# FubarinoMini_v20.net
KiCad netlist of a schematic drawn in EAGLE
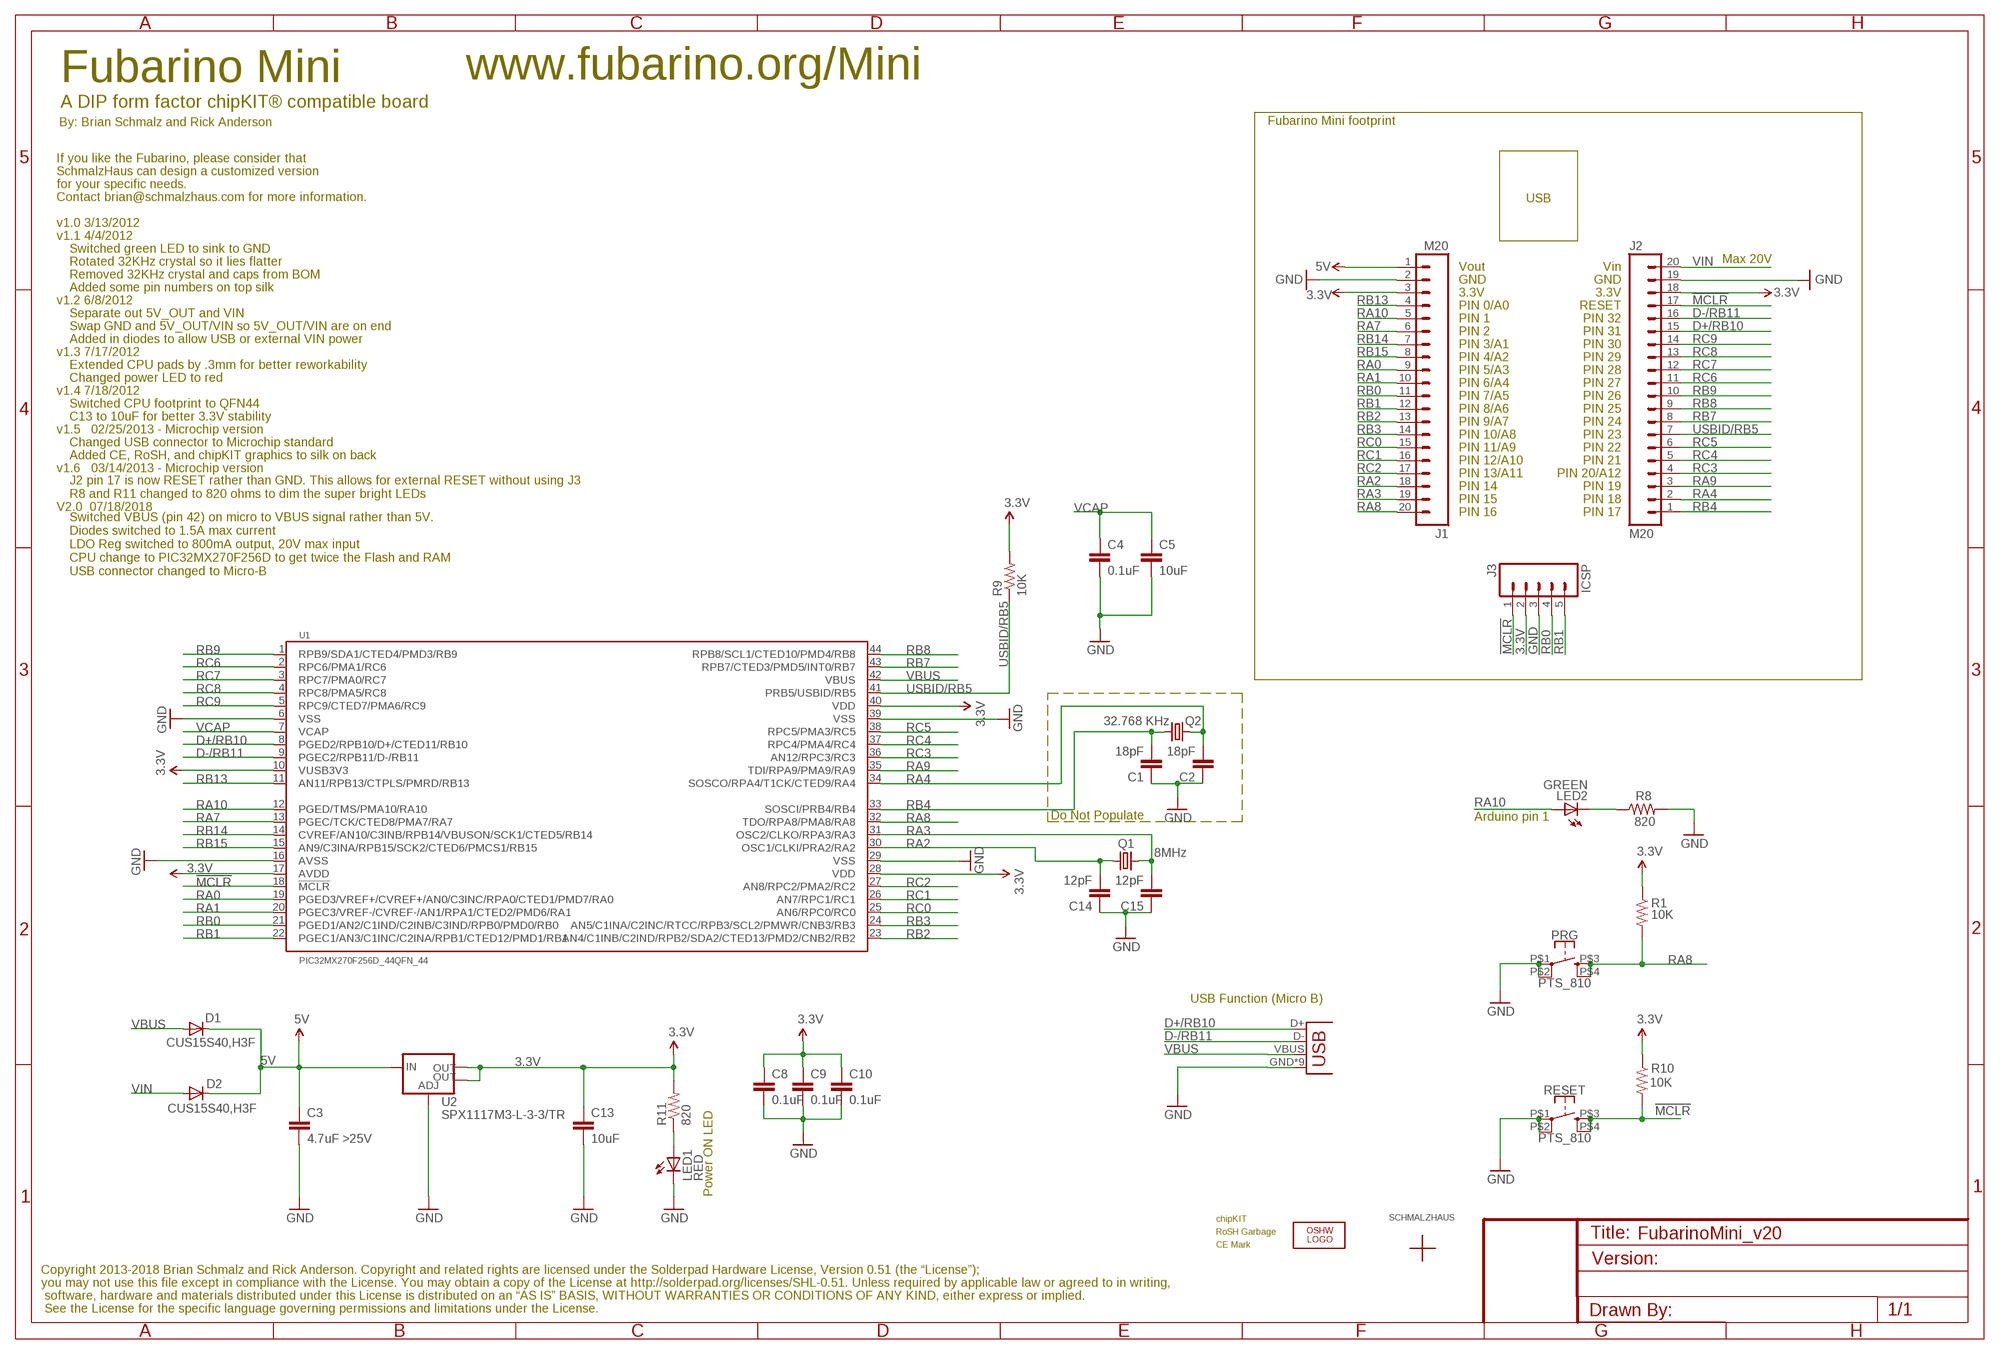
[diagram p0: schematic, sheet 1]

(export (version "E")
  (design (tool "Eeschema 10.0.6"))
  (components
    (comp (ref "C1")
      (value "18pF")
      (footprint "eagle-import:0603-CAP")
      (libsource (lib "eagle-import") (part "SparkFun_CAP0603-CAP"))
    )
    (comp (ref "C2")
      (value "18pF")
      (footprint "eagle-import:0603-CAP")
      (libsource (lib "eagle-import") (part "SparkFun_CAP0603-CAP"))
    )
    (comp (ref "C3")
      (value "4.7uF >25V")
      (footprint "eagle-import:0603-CAP")
      (libsource (lib "eagle-import") (part "SparkFun_CAP0603-CAP"))
    )
    (comp (ref "C4")
      (value "0.1uF")
      (footprint "eagle-import:0603-CAP")
      (libsource (lib "eagle-import") (part "SparkFun_CAP0603-CAP"))
    )
    (comp (ref "C5")
      (value "10uF")
      (footprint "eagle-import:0805")
      (libsource (lib "eagle-import") (part "CAP0805"))
    )
    (comp (ref "C8")
      (value "0.1uF")
      (footprint "eagle-import:0603-CAP")
      (libsource (lib "eagle-import") (part "SparkFun_CAP0603-CAP"))
    )
    (comp (ref "C9")
      (value "0.1uF")
      (footprint "eagle-import:0603-CAP")
      (libsource (lib "eagle-import") (part "SparkFun_CAP0603-CAP"))
    )
    (comp (ref "C10")
      (value "0.1uF")
      (footprint "eagle-import:0603")
      (libsource (lib "eagle-import") (part "CAP0603"))
    )
    (comp (ref "C13")
      (value "10uF")
      (footprint "eagle-import:0805")
      (libsource (lib "eagle-import") (part "SparkFun02-20-08_CAP0805"))
    )
    (comp (ref "C14")
      (value "12pF")
      (footprint "eagle-import:0603-CAP")
      (libsource (lib "eagle-import") (part "SparkFun_CAP0603-CAP"))
    )
    (comp (ref "C15")
      (value "12pF")
      (footprint "eagle-import:0603-CAP")
      (libsource (lib "eagle-import") (part "SparkFun_CAP0603-CAP"))
    )
    (comp (ref "D1")
      (value "CUS15S40,H3F")
      (footprint "eagle-import:SOD-323")
      (libsource (lib "eagle-import") (part "DIODESOD"))
    )
    (comp (ref "D2")
      (value "CUS15S40,H3F")
      (footprint "eagle-import:SOD-323")
      (libsource (lib "eagle-import") (part "DIODESOD"))
    )
    (comp (ref "ICSP")
      (value "J3")
      (footprint "eagle-import:1X05_NOSILK")
      (libsource (lib "eagle-import") (part "M05NOSLILK"))
    )
    (comp (ref "J1")
      (value "M20")
      (footprint "eagle-import:1X20_NO_PIN1")
      (libsource (lib "eagle-import") (part "M20"))
    )
    (comp (ref "J2")
      (value "M20")
      (footprint "eagle-import:1X20_NO_PIN1")
      (libsource (lib "eagle-import") (part "M20"))
    )
    (comp (ref "LED1")
      (value "RED")
      (footprint "eagle-import:LED-0603")
      (libsource (lib "eagle-import") (part "LED0603"))
    )
    (comp (ref "LED2")
      (value "GREEN")
      (footprint "eagle-import:LED-0603")
      (libsource (lib "eagle-import") (part "LED0603"))
    )
    (comp (ref "LOGO1")
      (value "OSHW_LOGO_8MILX0070-NT")
      (footprint "eagle-import:OSHW_8X70_NOTEXT")
      (libsource (lib "eagle-import") (part "OSHW_LOGO_8MILX0070-NT"))
    )
    (comp (ref "PRG")
      (value "PTS_810")
      (footprint "eagle-import:PTS_810")
      (libsource (lib "eagle-import") (part "PTS_810"))
    )
    (comp (ref "Q1")
      (value "8MHz")
      (footprint "eagle-import:NX3225GD")
      (libsource (lib "eagle-import") (part "NX3225GD"))
    )
    (comp (ref "Q2")
      (value "32.768 KHz")
      (footprint "eagle-import:TC26H")
      (libsource (lib "eagle-import") (part "CRYSTALTC26H"))
    )
    (comp (ref "R1")
      (value "10K")
      (footprint "eagle-import:0603-RES")
      (libsource (lib "eagle-import") (part "RESISTOR0603-RES"))
    )
    (comp (ref "R8")
      (value "820")
      (footprint "eagle-import:0603-RES")
      (libsource (lib "eagle-import") (part "RESISTOR0603-RES"))
    )
    (comp (ref "R9")
      (value "10K")
      (footprint "eagle-import:0603-RES")
      (libsource (lib "eagle-import") (part "RESISTOR0603-RES"))
    )
    (comp (ref "R10")
      (value "10K")
      (footprint "eagle-import:0603-RES")
      (libsource (lib "eagle-import") (part "RESISTOR0603-RES"))
    )
    (comp (ref "R11")
      (value "820")
      (footprint "eagle-import:0603-RES")
      (libsource (lib "eagle-import") (part "RESISTOR0603-RES"))
    )
    (comp (ref "RESET")
      (value "PTS_810")
      (footprint "eagle-import:PTS_810")
      (libsource (lib "eagle-import") (part "PTS_810"))
    )
    (comp (ref "U$1")
      (value "SCHMALZHAUSSCHMALZHAUS_SMALL")
      (footprint "eagle-import:SCHMALZHAUS_SMALL")
      (libsource (lib "eagle-import") (part "SCHMALZHAUSSCHMALZHAUS_SMALL"))
    )
    (comp (ref "U$2")
      (value "CE_MARK5MM")
      (footprint "eagle-import:CE_5MM")
      (libsource (lib "eagle-import") (part "CE_MARK5MM"))
    )
    (comp (ref "U$3")
      (value "ROSH_GARBAGE")
      (footprint "eagle-import:ROHS_GARBAGE_5MM")
      (libsource (lib "eagle-import") (part "ROSH_GARBAGE"))
    )
    (comp (ref "U$4")
      (value "CHIPKIT2MM")
      (footprint "eagle-import:CHIPKIT_2MM")
      (libsource (lib "eagle-import") (part "CHIPKIT2MM"))
    )
    (comp (ref "U$5")
      (value "USBMICROB")
      (footprint "eagle-import:USB-MICROB_FCI_PINS")
      (libsource (lib "eagle-import") (part "USBMICROB"))
    )
    (comp (ref "U1")
      (value "PIC32MX270F256D_44QFN_44")
      (footprint "eagle-import:QFN-44-8X8-NOPAD")
      (libsource (lib "eagle-import") (part "PIC32MX2XX_44QFN44"))
    )
    (comp (ref "U2")
      (value "SPX1117M3-L-3-3/TR")
      (footprint "eagle-import:SOT223")
      (libsource (lib "eagle-import") (part "V_REG_LM1117SOT223"))
    )
  )
  (nets
    (net (code "1") (name "/D+{slash}RB10") (class "Default")
      (node (ref "J2") (pin "15") (pinfunction "15_15") (pintype "passive"))
      (node (ref "U$5") (pin "D+") (pinfunction "D+_D+") (pintype "bidirectional"))
      (node (ref "U1") (pin "8") (pinfunction "PGED2/RPB10/D+/CTED11/RB10_8") (pintype "bidirectional"))
    )
    (net (code "2") (name "/D-{slash}RB11") (class "Default")
      (node (ref "J2") (pin "16") (pinfunction "16_16") (pintype "passive"))
      (node (ref "U$5") (pin "D-") (pinfunction "D-_D-") (pintype "bidirectional"))
      (node (ref "U1") (pin "9") (pinfunction "PGEC2/RPB11/D-/RB11_9") (pintype "bidirectional"))
    )
    (net (code "3") (name "/RA0") (class "Default")
      (node (ref "J1") (pin "9") (pinfunction "9_9") (pintype "passive"))
      (node (ref "U1") (pin "19") (pinfunction "PGED3/VREF+/CVREF+/AN0/C3INC/RPA0/CTED1/PMD7/RA0_19") (pintype "bidirectional"))
    )
    (net (code "4") (name "/RA1") (class "Default")
      (node (ref "J1") (pin "10") (pinfunction "10_10") (pintype "passive"))
      (node (ref "U1") (pin "20") (pinfunction "PGEC3/VREF-/CVREF-/AN1/RPA1/CTED2/PMD6/RA1_20") (pintype "bidirectional"))
    )
    (net (code "5") (name "/RA2") (class "Default")
      (node (ref "C14") (pin "2") (pinfunction "2_2") (pintype "passive"))
      (node (ref "J1") (pin "18") (pinfunction "18_18") (pintype "passive"))
      (node (ref "Q1") (pin "P$1") (pinfunction "1_P$1") (pintype "passive"))
      (node (ref "U1") (pin "30") (pinfunction "OSC1/CLKI/PRA2/RA2_30") (pintype "bidirectional"))
    )
    (net (code "6") (name "/RA3") (class "Default")
      (node (ref "C15") (pin "2") (pinfunction "2_2") (pintype "passive"))
      (node (ref "J1") (pin "19") (pinfunction "19_19") (pintype "passive"))
      (node (ref "Q1") (pin "P$2") (pinfunction "2_P$2") (pintype "passive"))
      (node (ref "U1") (pin "31") (pinfunction "OSC2/CLKO/RPA3/RA3_31") (pintype "bidirectional"))
    )
    (net (code "7") (name "/RA4") (class "Default")
      (node (ref "C2") (pin "2") (pinfunction "2_2") (pintype "passive"))
      (node (ref "J2") (pin "2") (pinfunction "2_2") (pintype "passive"))
      (node (ref "Q2") (pin "1") (pinfunction "1_1") (pintype "passive"))
      (node (ref "U1") (pin "34") (pinfunction "SOSCO/RPA4/T1CK/CTED9/RA4_34") (pintype "bidirectional"))
    )
    (net (code "8") (name "/RA7") (class "Default")
      (node (ref "J1") (pin "6") (pinfunction "6_6") (pintype "passive"))
      (node (ref "U1") (pin "13") (pinfunction "PGEC/TCK/CTED8/PMA7/RA7_13") (pintype "bidirectional"))
    )
    (net (code "9") (name "/RA8") (class "Default")
      (node (ref "J1") (pin "20") (pinfunction "20_20") (pintype "passive"))
      (node (ref "PRG") (pin "P$3") (pinfunction "3_P$3") (pintype "passive"))
      (node (ref "PRG") (pin "P$4") (pinfunction "4_P$4") (pintype "passive"))
      (node (ref "R1") (pin "2") (pinfunction "2_2") (pintype "passive"))
      (node (ref "U1") (pin "32") (pinfunction "TDO/RPA8/PMA8/RA8_32") (pintype "bidirectional"))
    )
    (net (code "10") (name "/RA9") (class "Default")
      (node (ref "J2") (pin "3") (pinfunction "3_3") (pintype "passive"))
      (node (ref "U1") (pin "35") (pinfunction "TDI/RPA9/PMA9/RA9_35") (pintype "bidirectional"))
    )
    (net (code "11") (name "/RA10") (class "Default")
      (node (ref "J1") (pin "5") (pinfunction "5_5") (pintype "passive"))
      (node (ref "LED2") (pin "A") (pinfunction "A_A") (pintype "passive"))
      (node (ref "U1") (pin "12") (pinfunction "PGED/TMS/PMA10/RA10_12") (pintype "bidirectional"))
    )
    (net (code "12") (name "/RB0") (class "Default")
      (node (ref "ICSP") (pin "4") (pinfunction "4_4") (pintype "passive"))
      (node (ref "J1") (pin "11") (pinfunction "11_11") (pintype "passive"))
      (node (ref "U1") (pin "21") (pinfunction "PGED1/AN2/C1IND/C2INB/C3IND/RPB0/PMD0/RB0_21") (pintype "bidirectional"))
    )
    (net (code "13") (name "/RB1") (class "Default")
      (node (ref "ICSP") (pin "5") (pinfunction "5_5") (pintype "passive"))
      (node (ref "J1") (pin "12") (pinfunction "12_12") (pintype "passive"))
      (node (ref "U1") (pin "22") (pinfunction "PGEC1/AN3/C1INC/C2INA/RPB1/CTED12/PMD1/RB1_22") (pintype "bidirectional"))
    )
    (net (code "14") (name "/RB2") (class "Default")
      (node (ref "J1") (pin "13") (pinfunction "13_13") (pintype "passive"))
      (node (ref "U1") (pin "23") (pinfunction "AN4/C1INB/C2IND/RPB2/SDA2/CTED13/PMD2/CNB2/RB2_23") (pintype "bidirectional"))
    )
    (net (code "15") (name "/RB3") (class "Default")
      (node (ref "J1") (pin "14") (pinfunction "14_14") (pintype "passive"))
      (node (ref "U1") (pin "24") (pinfunction "AN5/C1INA/C2INC/RTCC/RPB3/SCL2/PMWR/CNB3/RB3_24") (pintype "bidirectional"))
    )
    (net (code "16") (name "/RB4") (class "Default")
      (node (ref "C1") (pin "2") (pinfunction "2_2") (pintype "passive"))
      (node (ref "J2") (pin "1") (pinfunction "1_1") (pintype "passive"))
      (node (ref "Q2") (pin "2") (pinfunction "2_2") (pintype "passive"))
      (node (ref "U1") (pin "33") (pinfunction "SOSCI/PRB4/RB4_33") (pintype "bidirectional"))
    )
    (net (code "17") (name "/RB7") (class "Default")
      (node (ref "J2") (pin "8") (pinfunction "8_8") (pintype "passive"))
      (node (ref "U1") (pin "43") (pinfunction "RPB7/CTED3/PMD5/INT0/RB7_43") (pintype "bidirectional"))
    )
    (net (code "18") (name "/RB8") (class "Default")
      (node (ref "J2") (pin "9") (pinfunction "9_9") (pintype "passive"))
      (node (ref "U1") (pin "44") (pinfunction "RPB8/SCL1/CTED10/PMD4/RB8_44") (pintype "bidirectional"))
    )
    (net (code "19") (name "/RB9") (class "Default")
      (node (ref "J2") (pin "10") (pinfunction "10_10") (pintype "passive"))
      (node (ref "U1") (pin "1") (pinfunction "RPB9/SDA1/CTED4/PMD3/RB9_1") (pintype "bidirectional"))
    )
    (net (code "20") (name "/RB13") (class "Default")
      (node (ref "J1") (pin "4") (pinfunction "4_4") (pintype "passive"))
      (node (ref "U1") (pin "11") (pinfunction "AN11/RPB13/CTPLS/PMRD/RB13_11") (pintype "bidirectional"))
    )
    (net (code "21") (name "/RB14") (class "Default")
      (node (ref "J1") (pin "7") (pinfunction "7_7") (pintype "passive"))
      (node (ref "U1") (pin "14") (pinfunction "CVREF/AN10/C3INB/RPB14/VBUSON/SCK1/CTED5/RB14_14") (pintype "bidirectional"))
    )
    (net (code "22") (name "/RB15") (class "Default")
      (node (ref "J1") (pin "8") (pinfunction "8_8") (pintype "passive"))
      (node (ref "U1") (pin "15") (pinfunction "AN9/C3INA/RPB15/SCK2/CTED6/PMCS1/RB15_15") (pintype "bidirectional"))
    )
    (net (code "23") (name "/RC0") (class "Default")
      (node (ref "J1") (pin "15") (pinfunction "15_15") (pintype "passive"))
      (node (ref "U1") (pin "25") (pinfunction "AN6/RPC0/RC0_25") (pintype "bidirectional"))
    )
    (net (code "24") (name "/RC1") (class "Default")
      (node (ref "J1") (pin "16") (pinfunction "16_16") (pintype "passive"))
      (node (ref "U1") (pin "26") (pinfunction "AN7/RPC1/RC1_26") (pintype "bidirectional"))
    )
    (net (code "25") (name "/RC2") (class "Default")
      (node (ref "J1") (pin "17") (pinfunction "17_17") (pintype "passive"))
      (node (ref "U1") (pin "27") (pinfunction "AN8/RPC2/PMA2/RC2_27") (pintype "bidirectional"))
    )
    (net (code "26") (name "/RC3") (class "Default")
      (node (ref "J2") (pin "4") (pinfunction "4_4") (pintype "passive"))
      (node (ref "U1") (pin "36") (pinfunction "AN12/RPC3/RC3_36") (pintype "bidirectional"))
    )
    (net (code "27") (name "/RC4") (class "Default")
      (node (ref "J2") (pin "5") (pinfunction "5_5") (pintype "passive"))
      (node (ref "U1") (pin "37") (pinfunction "RPC4/PMA4/RC4_37") (pintype "bidirectional"))
    )
    (net (code "28") (name "/RC5") (class "Default")
      (node (ref "J2") (pin "6") (pinfunction "6_6") (pintype "passive"))
      (node (ref "U1") (pin "38") (pinfunction "RPC5/PMA3/RC5_38") (pintype "bidirectional"))
    )
    (net (code "29") (name "/RC6") (class "Default")
      (node (ref "J2") (pin "11") (pinfunction "11_11") (pintype "passive"))
      (node (ref "U1") (pin "2") (pinfunction "RPC6/PMA1/RC6_2") (pintype "bidirectional"))
    )
    (net (code "30") (name "/RC7") (class "Default")
      (node (ref "J2") (pin "12") (pinfunction "12_12") (pintype "passive"))
      (node (ref "U1") (pin "3") (pinfunction "RPC7/PMA0/RC7_3") (pintype "bidirectional"))
    )
    (net (code "31") (name "/RC8") (class "Default")
      (node (ref "J2") (pin "13") (pinfunction "13_13") (pintype "passive"))
      (node (ref "U1") (pin "4") (pinfunction "RPC8/PMA5/RC8_4") (pintype "bidirectional"))
    )
    (net (code "32") (name "/RC9") (class "Default")
      (node (ref "J2") (pin "14") (pinfunction "14_14") (pintype "passive"))
      (node (ref "U1") (pin "5") (pinfunction "RPC9/CTED7/PMA6/RC9_5") (pintype "bidirectional"))
    )
    (net (code "33") (name "/USBID{slash}RB5") (class "Default")
      (node (ref "J2") (pin "7") (pinfunction "7_7") (pintype "passive"))
      (node (ref "R9") (pin "1") (pinfunction "1_1") (pintype "passive"))
      (node (ref "U1") (pin "41") (pinfunction "PRB5/USBID/RB5_41") (pintype "bidirectional"))
    )
    (net (code "34") (name "/VBUS") (class "Default")
      (node (ref "D1") (pin "2") (pinfunction "A_2") (pintype "passive"))
      (node (ref "U$5") (pin "VBUS") (pinfunction "VBUS_VBUS") (pintype "bidirectional"))
      (node (ref "U1") (pin "42") (pinfunction "VBUS_42") (pintype "bidirectional"))
    )
    (net (code "35") (name "/VCAP") (class "Default")
      (node (ref "C4") (pin "1") (pinfunction "1_1") (pintype "passive"))
      (node (ref "C5") (pin "1") (pinfunction "1_1") (pintype "passive"))
      (node (ref "U1") (pin "7") (pinfunction "VCAP_7") (pintype "bidirectional"))
    )
    (net (code "36") (name "/VIN") (class "Default")
      (node (ref "D2") (pin "2") (pinfunction "A_2") (pintype "passive"))
      (node (ref "J2") (pin "20") (pinfunction "20_20") (pintype "passive"))
    )
    (net (code "37") (name "/~{MCLR}") (class "Default")
      (node (ref "ICSP") (pin "1") (pinfunction "1_1") (pintype "passive"))
      (node (ref "J2") (pin "17") (pinfunction "17_17") (pintype "passive"))
      (node (ref "R10") (pin "2") (pinfunction "2_2") (pintype "passive"))
      (node (ref "RESET") (pin "P$3") (pinfunction "3_P$3") (pintype "passive"))
      (node (ref "RESET") (pin "P$4") (pinfunction "4_P$4") (pintype "passive"))
      (node (ref "U1") (pin "18") (pinfunction "~{MCLR}_18") (pintype "bidirectional"))
    )
    (net (code "38") (name "3.3V") (class "Default")
      (node (ref "C10") (pin "1") (pinfunction "1_1") (pintype "passive"))
      (node (ref "C13") (pin "1") (pinfunction "1_1") (pintype "passive"))
      (node (ref "C8") (pin "1") (pinfunction "1_1") (pintype "passive"))
      (node (ref "C9") (pin "1") (pinfunction "1_1") (pintype "passive"))
      (node (ref "ICSP") (pin "2") (pinfunction "2_2") (pintype "passive"))
      (node (ref "J1") (pin "3") (pinfunction "3_3") (pintype "passive"))
      (node (ref "J2") (pin "18") (pinfunction "18_18") (pintype "passive"))
      (node (ref "R1") (pin "1") (pinfunction "1_1") (pintype "passive"))
      (node (ref "R10") (pin "1") (pinfunction "1_1") (pintype "passive"))
      (node (ref "R11") (pin "2") (pinfunction "2_2") (pintype "passive"))
      (node (ref "R9") (pin "2") (pinfunction "2_2") (pintype "passive"))
      (node (ref "U1") (pin "10") (pinfunction "VUSB3V3_10") (pintype "bidirectional"))
      (node (ref "U1") (pin "17") (pinfunction "AVDD_17") (pintype "bidirectional"))
      (node (ref "U1") (pin "28") (pinfunction "VDD_28") (pintype "bidirectional"))
      (node (ref "U1") (pin "40") (pinfunction "VDD_40") (pintype "bidirectional"))
      (node (ref "U2") (pin "2") (pinfunction "OUT_2") (pintype "output"))
      (node (ref "U2") (pin "4") (pinfunction "OUT_4") (pintype "output"))
    )
    (net (code "39") (name "5V") (class "Default")
      (node (ref "C3") (pin "1") (pinfunction "1_1") (pintype "passive"))
      (node (ref "D1") (pin "1") (pinfunction "C_1") (pintype "passive"))
      (node (ref "D2") (pin "1") (pinfunction "C_1") (pintype "passive"))
      (node (ref "J1") (pin "1") (pinfunction "1_1") (pintype "passive"))
      (node (ref "U2") (pin "3") (pinfunction "IN_3") (pintype "input"))
    )
    (net (code "40") (name "GND") (class "Default")
      (node (ref "C1") (pin "1") (pinfunction "1_1") (pintype "passive"))
      (node (ref "C10") (pin "2") (pinfunction "2_2") (pintype "passive"))
      (node (ref "C13") (pin "2") (pinfunction "2_2") (pintype "passive"))
      (node (ref "C14") (pin "1") (pinfunction "1_1") (pintype "passive"))
      (node (ref "C15") (pin "1") (pinfunction "1_1") (pintype "passive"))
      (node (ref "C2") (pin "1") (pinfunction "1_1") (pintype "passive"))
      (node (ref "C3") (pin "2") (pinfunction "2_2") (pintype "passive"))
      (node (ref "C4") (pin "2") (pinfunction "2_2") (pintype "passive"))
      (node (ref "C5") (pin "2") (pinfunction "2_2") (pintype "passive"))
      (node (ref "C8") (pin "2") (pinfunction "2_2") (pintype "passive"))
      (node (ref "C9") (pin "2") (pinfunction "2_2") (pintype "passive"))
      (node (ref "ICSP") (pin "3") (pinfunction "3_3") (pintype "passive"))
      (node (ref "J1") (pin "2") (pinfunction "2_2") (pintype "passive"))
      (node (ref "J2") (pin "19") (pinfunction "19_19") (pintype "passive"))
      (node (ref "LED1") (pin "C") (pinfunction "C_C") (pintype "passive"))
      (node (ref "PRG") (pin "P$1") (pinfunction "1_P$1") (pintype "passive"))
      (node (ref "PRG") (pin "P$2") (pinfunction "2_P$2") (pintype "passive"))
      (node (ref "R8") (pin "2") (pinfunction "2_2") (pintype "passive"))
      (node (ref "RESET") (pin "P$1") (pinfunction "1_P$1") (pintype "passive"))
      (node (ref "RESET") (pin "P$2") (pinfunction "2_P$2") (pintype "passive"))
      (node (ref "U$5") (pin "GND") (pinfunction "GND_GND") (pintype "bidirectional"))
      (node (ref "U$5") (pin "GND@1") (pinfunction "GND_GND@1") (pintype "bidirectional"))
      (node (ref "U$5") (pin "GND@2") (pinfunction "GND_GND@2") (pintype "bidirectional"))
      (node (ref "U$5") (pin "GND@3") (pinfunction "GND_GND@3") (pintype "bidirectional"))
      (node (ref "U$5") (pin "GND@4") (pinfunction "GND_GND@4") (pintype "bidirectional"))
      (node (ref "U$5") (pin "GND@5") (pinfunction "GND_GND@5") (pintype "bidirectional"))
      (node (ref "U$5") (pin "GND@6") (pinfunction "GND_GND@6") (pintype "bidirectional"))
      (node (ref "U$5") (pin "GND@7") (pinfunction "GND_GND@7") (pintype "bidirectional"))
      (node (ref "U$5") (pin "GND@8") (pinfunction "GND_GND@8") (pintype "bidirectional"))
      (node (ref "U1") (pin "16") (pinfunction "AVSS_16") (pintype "bidirectional"))
      (node (ref "U1") (pin "29") (pinfunction "VSS_29") (pintype "bidirectional"))
      (node (ref "U1") (pin "39") (pinfunction "VSS_39") (pintype "bidirectional"))
      (node (ref "U1") (pin "6") (pinfunction "VSS_6") (pintype "bidirectional"))
      (node (ref "U2") (pin "1") (pinfunction "ADJ_1") (pintype "input"))
    )
    (net (code "41") (name "Net-(LED1-PadA)") (class "Default")
      (node (ref "LED1") (pin "A") (pinfunction "A_A") (pintype "passive"))
      (node (ref "R11") (pin "1") (pinfunction "1_1") (pintype "passive"))
    )
    (net (code "42") (name "Net-(LED2-PadC)") (class "Default")
      (node (ref "LED2") (pin "C") (pinfunction "C_C") (pintype "passive"))
      (node (ref "R8") (pin "1") (pinfunction "1_1") (pintype "passive"))
    )
  )
)
